# 01_Raspberry_Hat_6_Schematic.net
KiCad netlist of a schematic drawn in EAGLE
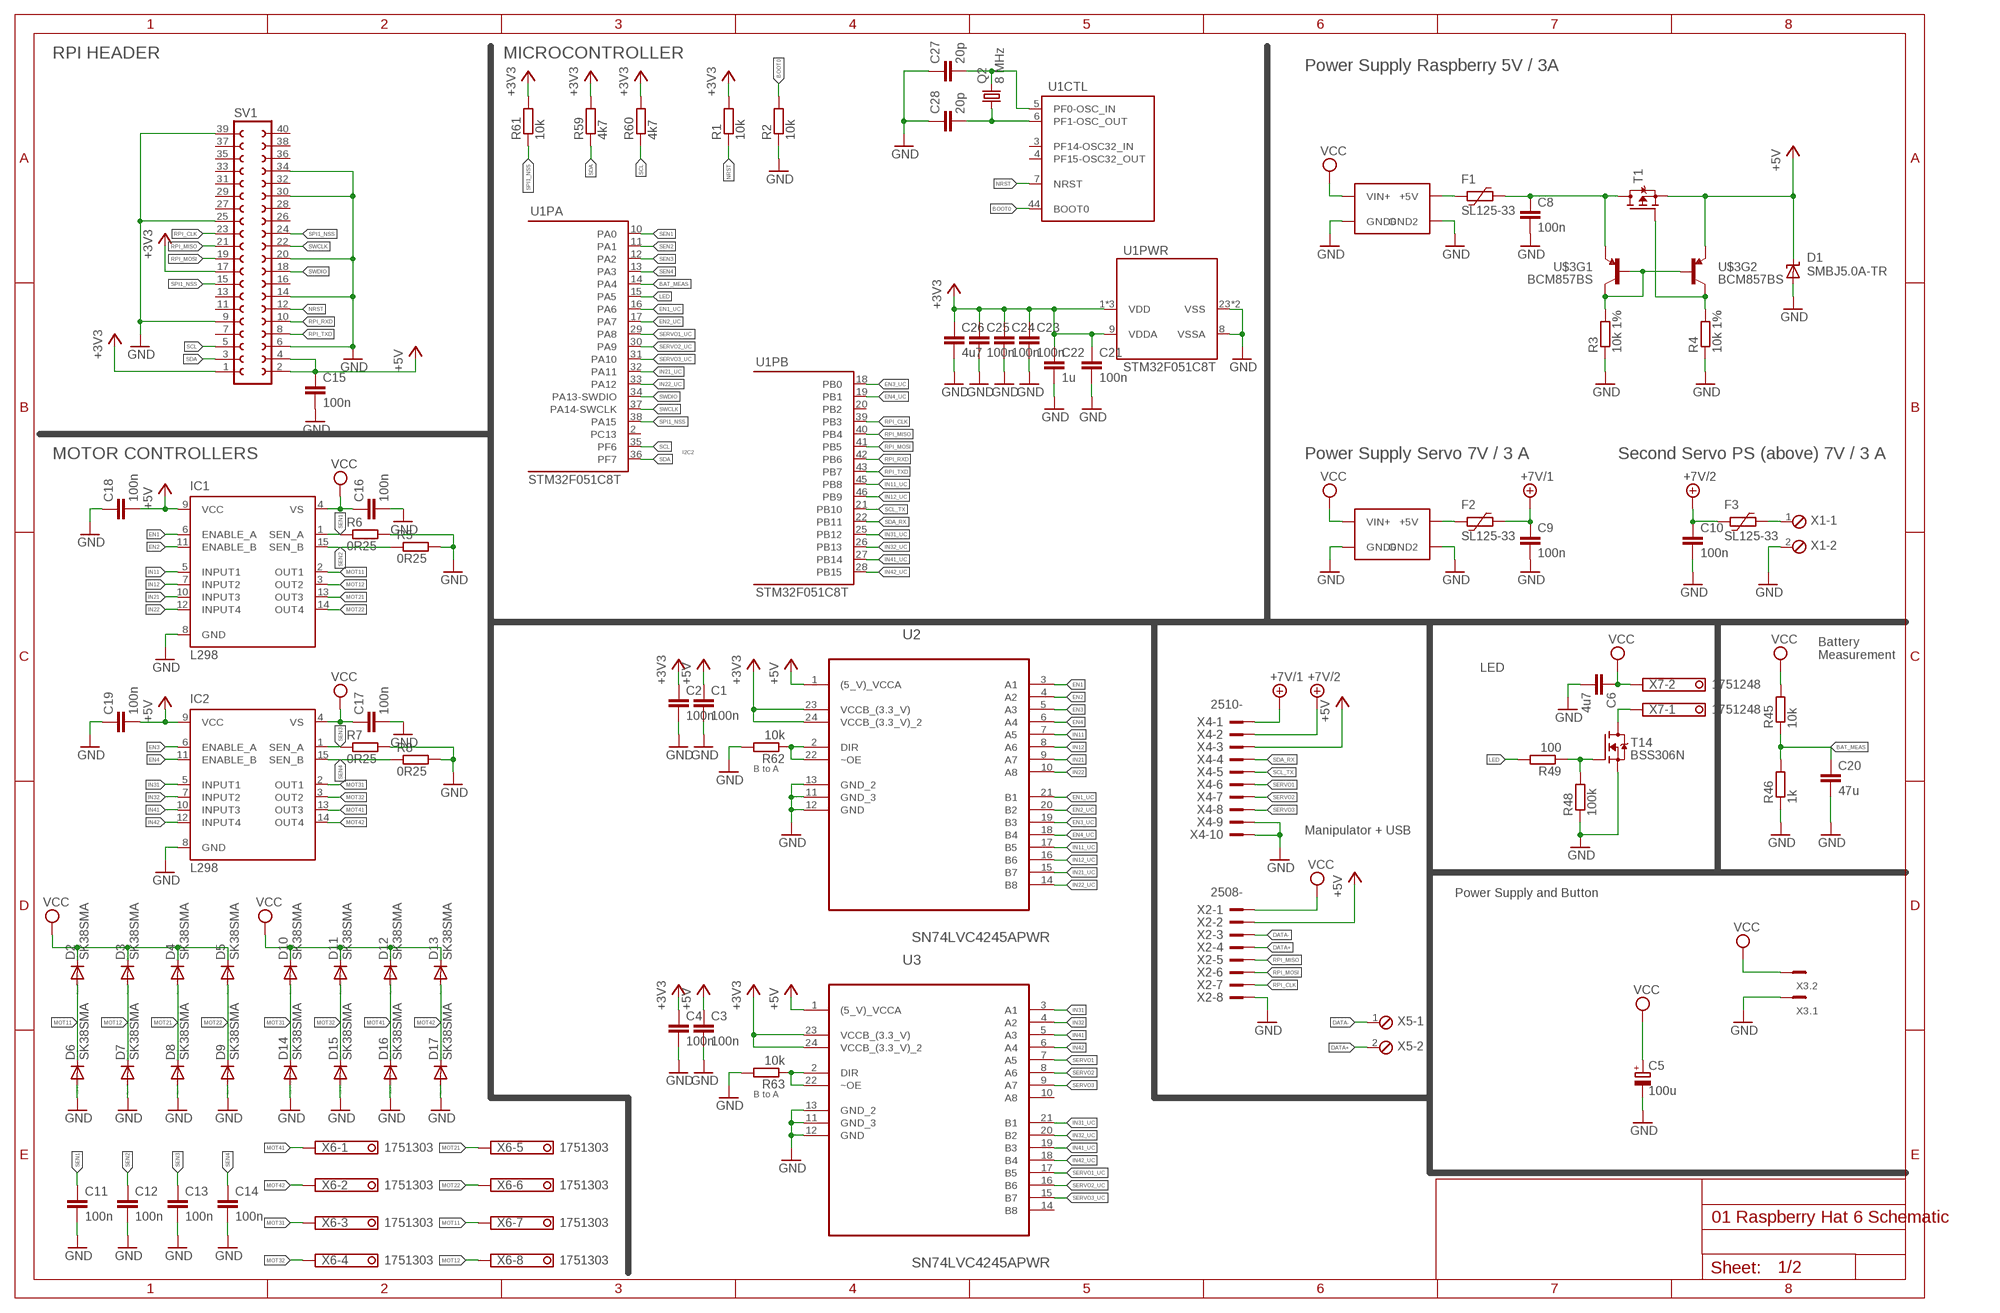
[diagram p0: schematic, sheet 1]
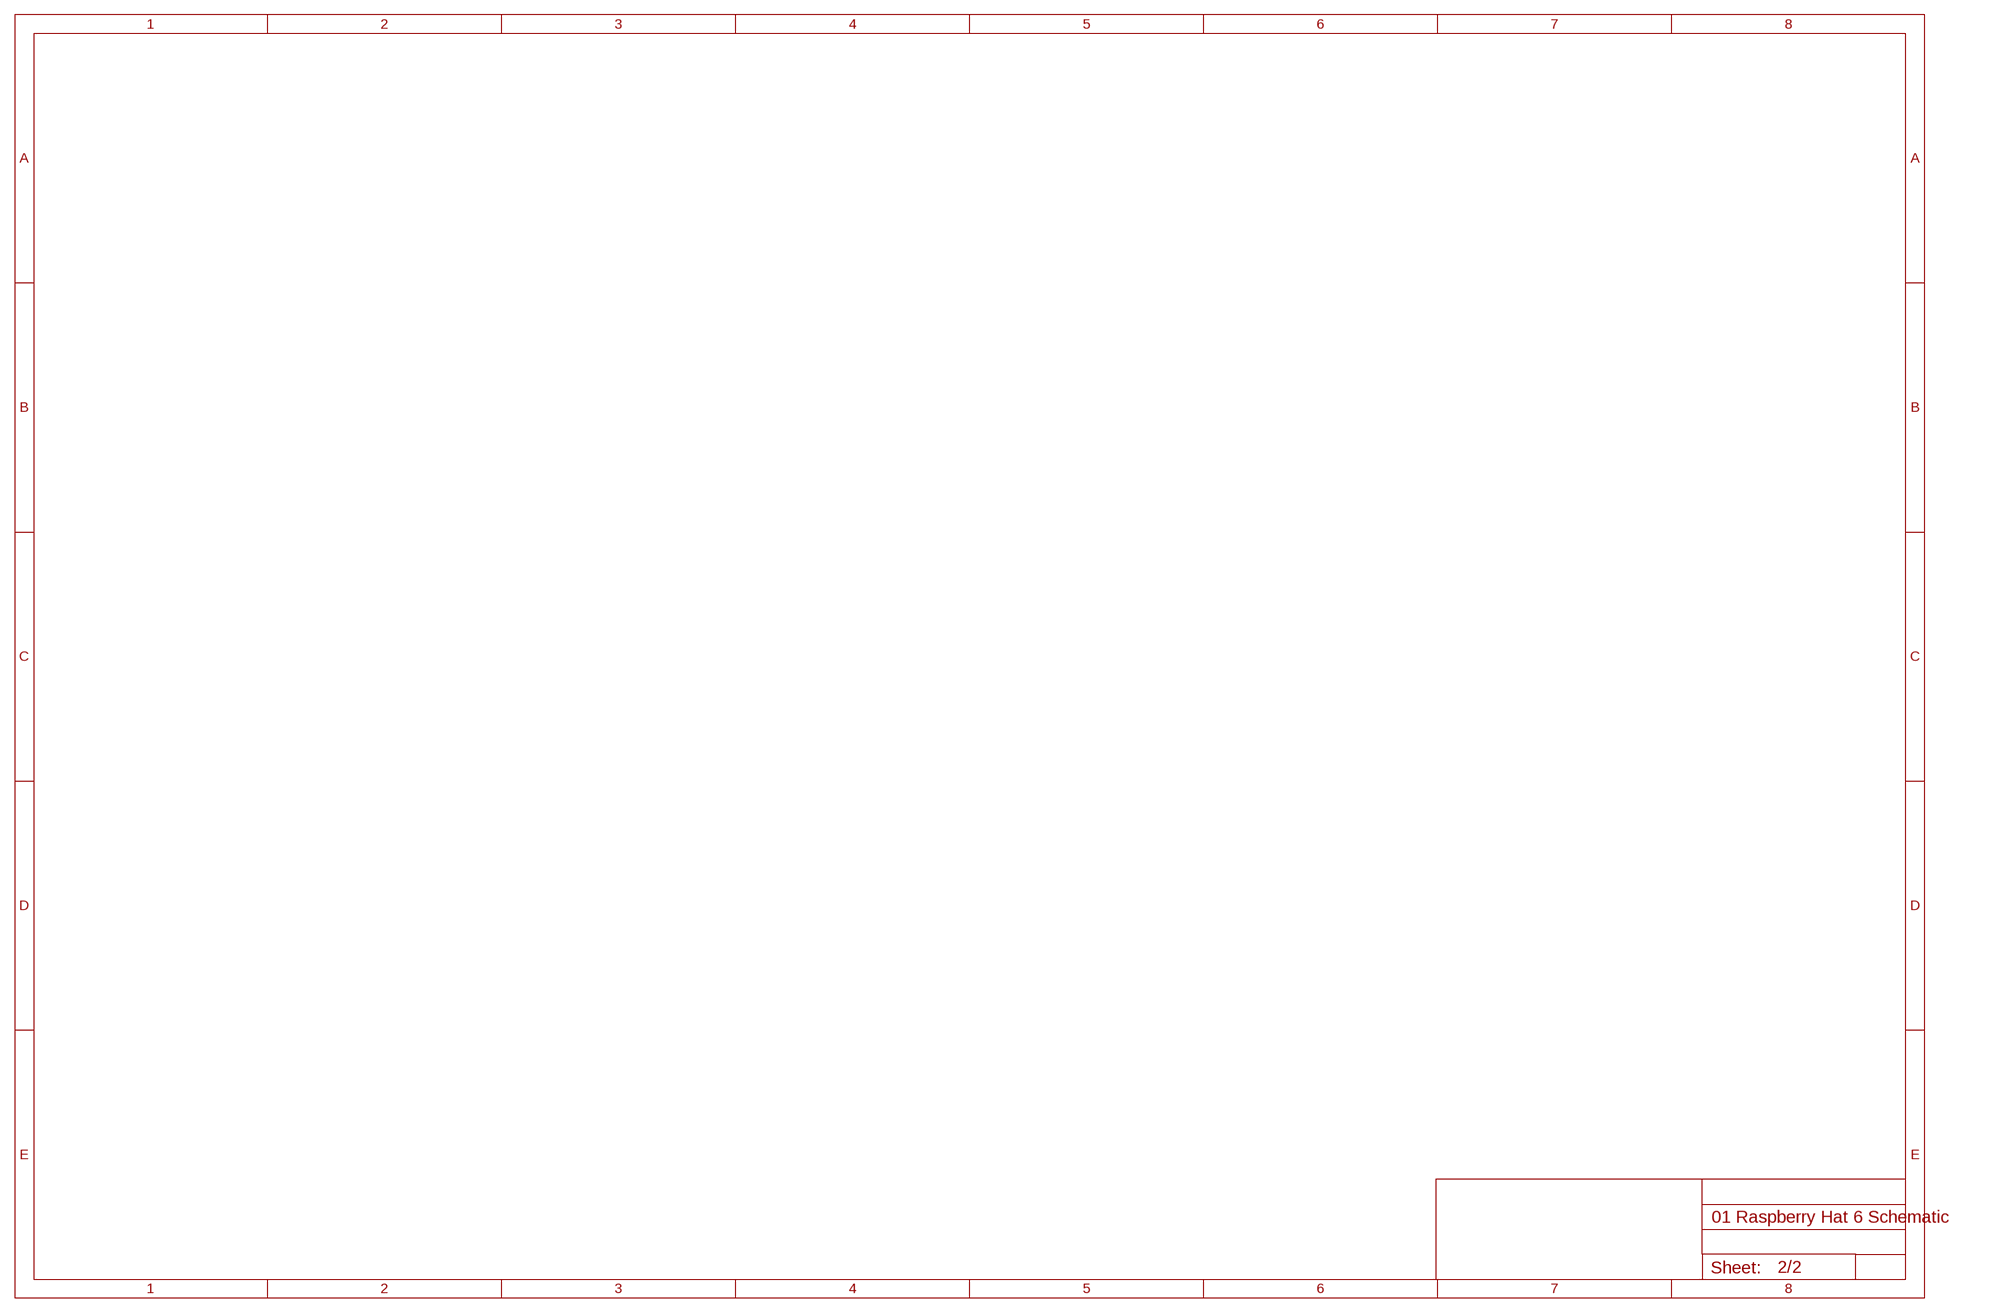
[diagram p1: schematic, sheet 2]

(export (version "E")
  (design (tool "Eeschema 10.0.6"))
  (components
    (comp (ref "C1")
      (value "100n")
      (footprint "eagle-import:C0805")
      (libsource (lib "eagle-import") (part "C-EUC0805"))
    )
    (comp (ref "C2")
      (value "100n")
      (footprint "eagle-import:C0805")
      (libsource (lib "eagle-import") (part "C-EUC0805"))
    )
    (comp (ref "C3")
      (value "100n")
      (footprint "eagle-import:C0805")
      (libsource (lib "eagle-import") (part "C-EUC0805"))
    )
    (comp (ref "C4")
      (value "100n")
      (footprint "eagle-import:C0805")
      (libsource (lib "eagle-import") (part "C-EUC0805"))
    )
    (comp (ref "C5")
      (value "100u")
      (footprint "eagle-import:153CLV-0807")
      (libsource (lib "eagle-import") (part "CPOL-EU153CLV-0807"))
    )
    (comp (ref "C6")
      (value "4u7")
      (footprint "eagle-import:C0805")
      (libsource (lib "eagle-import") (part "C-EUC0805"))
    )
    (comp (ref "C8")
      (value "100n")
      (footprint "eagle-import:C0805")
      (libsource (lib "eagle-import") (part "C-EUC0805"))
    )
    (comp (ref "C9")
      (value "100n")
      (footprint "eagle-import:C0805")
      (libsource (lib "eagle-import") (part "C-EUC0805"))
    )
    (comp (ref "C10")
      (value "100n")
      (footprint "eagle-import:C0805")
      (libsource (lib "eagle-import") (part "C-EUC0805"))
    )
    (comp (ref "C11")
      (value "100n")
      (footprint "eagle-import:C0805")
      (libsource (lib "eagle-import") (part "C-EUC0805"))
    )
    (comp (ref "C12")
      (value "100n")
      (footprint "eagle-import:C0805")
      (libsource (lib "eagle-import") (part "C-EUC0805"))
    )
    (comp (ref "C13")
      (value "100n")
      (footprint "eagle-import:C0805")
      (libsource (lib "eagle-import") (part "C-EUC0805"))
    )
    (comp (ref "C14")
      (value "100n")
      (footprint "eagle-import:C0805")
      (libsource (lib "eagle-import") (part "C-EUC0805"))
    )
    (comp (ref "C15")
      (value "100n")
      (footprint "eagle-import:C0805")
      (libsource (lib "eagle-import") (part "C-EUC0805"))
    )
    (comp (ref "C16")
      (value "100n")
      (footprint "eagle-import:C0805")
      (libsource (lib "eagle-import") (part "C-EUC0805"))
    )
    (comp (ref "C17")
      (value "100n")
      (footprint "eagle-import:C0805")
      (libsource (lib "eagle-import") (part "C-EUC0805"))
    )
    (comp (ref "C18")
      (value "100n")
      (footprint "eagle-import:C0805")
      (libsource (lib "eagle-import") (part "C-EUC0805"))
    )
    (comp (ref "C19")
      (value "100n")
      (footprint "eagle-import:C0805")
      (libsource (lib "eagle-import") (part "C-EUC0805"))
    )
    (comp (ref "C20")
      (value "47u")
      (footprint "eagle-import:C0805")
      (libsource (lib "eagle-import") (part "C-EUC0805"))
    )
    (comp (ref "C21")
      (value "100n")
      (footprint "eagle-import:C0805")
      (libsource (lib "eagle-import") (part "C-EUC0805"))
    )
    (comp (ref "C22")
      (value "1u")
      (footprint "eagle-import:C0805")
      (libsource (lib "eagle-import") (part "C-EUC0805"))
    )
    (comp (ref "C23")
      (value "100n")
      (footprint "eagle-import:C0805")
      (libsource (lib "eagle-import") (part "C-EUC0805"))
    )
    (comp (ref "C24")
      (value "100n")
      (footprint "eagle-import:C0805")
      (libsource (lib "eagle-import") (part "C-EUC0805"))
    )
    (comp (ref "C25")
      (value "100n")
      (footprint "eagle-import:C0805")
      (libsource (lib "eagle-import") (part "C-EUC0805"))
    )
    (comp (ref "C26")
      (value "4u7")
      (footprint "eagle-import:C0805")
      (libsource (lib "eagle-import") (part "C-EUC0805"))
    )
    (comp (ref "C27")
      (value "20p")
      (footprint "eagle-import:C0805")
      (libsource (lib "eagle-import") (part "C-EUC0805"))
    )
    (comp (ref "C28")
      (value "20p")
      (footprint "eagle-import:C0805")
      (libsource (lib "eagle-import") (part "C-EUC0805"))
    )
    (comp (ref "D1")
      (value "SMBJ5.0A-TR")
      (footprint "eagle-import:SMBJ")
      (libsource (lib "eagle-import") (part "SUPPRESSOR-SMBJ"))
    )
    (comp (ref "D2")
      (value "SK38SMA")
      (footprint "eagle-import:DO214AC")
      (libsource (lib "eagle-import") (part "DIODE-DO214AC"))
    )
    (comp (ref "D3")
      (value "SK38SMA")
      (footprint "eagle-import:DO214AC")
      (libsource (lib "eagle-import") (part "DIODE-DO214AC"))
    )
    (comp (ref "D4")
      (value "SK38SMA")
      (footprint "eagle-import:DO214AC")
      (libsource (lib "eagle-import") (part "DIODE-DO214AC"))
    )
    (comp (ref "D5")
      (value "SK38SMA")
      (footprint "eagle-import:DO214AC")
      (libsource (lib "eagle-import") (part "DIODE-DO214AC"))
    )
    (comp (ref "D6")
      (value "SK38SMA")
      (footprint "eagle-import:DO214AC")
      (libsource (lib "eagle-import") (part "DIODE-DO214AC"))
    )
    (comp (ref "D7")
      (value "SK38SMA")
      (footprint "eagle-import:DO214AC")
      (libsource (lib "eagle-import") (part "DIODE-DO214AC"))
    )
    (comp (ref "D8")
      (value "SK38SMA")
      (footprint "eagle-import:DO214AC")
      (libsource (lib "eagle-import") (part "DIODE-DO214AC"))
    )
    (comp (ref "D9")
      (value "SK38SMA")
      (footprint "eagle-import:DO214AC")
      (libsource (lib "eagle-import") (part "DIODE-DO214AC"))
    )
    (comp (ref "D10")
      (value "SK38SMA")
      (footprint "eagle-import:DO214AC")
      (libsource (lib "eagle-import") (part "DIODE-DO214AC"))
    )
    (comp (ref "D11")
      (value "SK38SMA")
      (footprint "eagle-import:DO214AC")
      (libsource (lib "eagle-import") (part "DIODE-DO214AC"))
    )
    (comp (ref "D12")
      (value "SK38SMA")
      (footprint "eagle-import:DO214AC")
      (libsource (lib "eagle-import") (part "DIODE-DO214AC"))
    )
    (comp (ref "D13")
      (value "SK38SMA")
      (footprint "eagle-import:DO214AC")
      (libsource (lib "eagle-import") (part "DIODE-DO214AC"))
    )
    (comp (ref "D14")
      (value "SK38SMA")
      (footprint "eagle-import:DO214AC")
      (libsource (lib "eagle-import") (part "DIODE-DO214AC"))
    )
    (comp (ref "D15")
      (value "SK38SMA")
      (footprint "eagle-import:DO214AC")
      (libsource (lib "eagle-import") (part "DIODE-DO214AC"))
    )
    (comp (ref "D16")
      (value "SK38SMA")
      (footprint "eagle-import:DO214AC")
      (libsource (lib "eagle-import") (part "DIODE-DO214AC"))
    )
    (comp (ref "D17")
      (value "SK38SMA")
      (footprint "eagle-import:DO214AC")
      (libsource (lib "eagle-import") (part "DIODE-DO214AC"))
    )
    (comp (ref "F1")
      (value "SL125-33")
      (footprint "eagle-import:2920L")
      (fields (field (name "MF") "Littelfuse") (field (name "MPN") "2920L050"))
      (libsource (lib "eagle-import") (part "?2920L050"))
    )
    (comp (ref "F2")
      (value "SL125-33")
      (footprint "eagle-import:2920L")
      (fields (field (name "MF") "Littelfuse") (field (name "MPN") "2920L050"))
      (libsource (lib "eagle-import") (part "?2920L050"))
    )
    (comp (ref "F3")
      (value "SL125-33")
      (footprint "eagle-import:2920L")
      (fields (field (name "MF") "Littelfuse") (field (name "MPN") "2920L050"))
      (libsource (lib "eagle-import") (part "?2920L050"))
    )
    (comp (ref "IC1")
      (value "L298")
      (footprint "eagle-import:MULTIWATT-15")
      (fields (field (name "MPN") "L298N"))
      (libsource (lib "eagle-import") (part "L298"))
    )
    (comp (ref "IC2")
      (value "L298")
      (footprint "eagle-import:MULTIWATT-15")
      (fields (field (name "MPN") "L298N"))
      (libsource (lib "eagle-import") (part "L298"))
    )
    (comp (ref "Q2")
      (value "8 MHz")
      (footprint "eagle-import:HC49UP")
      (libsource (lib "eagle-import") (part "CRYSTALHC49UP"))
    )
    (comp (ref "R1")
      (value "10k")
      (footprint "eagle-import:M0805")
      (libsource (lib "eagle-import") (part "resistor_R-EU_M0805"))
    )
    (comp (ref "R2")
      (value "10k")
      (footprint "eagle-import:M0805")
      (libsource (lib "eagle-import") (part "resistor_R-EU_M0805"))
    )
    (comp (ref "R3")
      (value "10k 1%")
      (footprint "eagle-import:M0805")
      (libsource (lib "eagle-import") (part "resistor_R-EU_M0805"))
    )
    (comp (ref "R4")
      (value "10k 1%")
      (footprint "eagle-import:M0805")
      (libsource (lib "eagle-import") (part "resistor_R-EU_M0805"))
    )
    (comp (ref "R5")
      (value "0R25")
      (footprint "eagle-import:R2512")
      (libsource (lib "eagle-import") (part "R-EU_R2512"))
    )
    (comp (ref "R6")
      (value "0R25")
      (footprint "eagle-import:R2512")
      (libsource (lib "eagle-import") (part "R-EU_R2512"))
    )
    (comp (ref "R7")
      (value "0R25")
      (footprint "eagle-import:R2512")
      (libsource (lib "eagle-import") (part "R-EU_R2512"))
    )
    (comp (ref "R8")
      (value "0R25")
      (footprint "eagle-import:R2512")
      (libsource (lib "eagle-import") (part "R-EU_R2512"))
    )
    (comp (ref "R45")
      (value "10k")
      (footprint "eagle-import:M0805")
      (libsource (lib "eagle-import") (part "resistor_R-EU_M0805"))
    )
    (comp (ref "R46")
      (value "1k")
      (footprint "eagle-import:M0805")
      (libsource (lib "eagle-import") (part "resistor_R-EU_M0805"))
    )
    (comp (ref "R48")
      (value "100k")
      (footprint "eagle-import:M0805")
      (libsource (lib "eagle-import") (part "resistor_R-EU_M0805"))
    )
    (comp (ref "R49")
      (value "100")
      (footprint "eagle-import:M0805")
      (libsource (lib "eagle-import") (part "resistor_R-EU_M0805"))
    )
    (comp (ref "R59")
      (value "4k7")
      (footprint "eagle-import:M0805")
      (libsource (lib "eagle-import") (part "resistor_R-EU_M0805"))
    )
    (comp (ref "R60")
      (value "4k7")
      (footprint "eagle-import:M0805")
      (libsource (lib "eagle-import") (part "resistor_R-EU_M0805"))
    )
    (comp (ref "R61")
      (value "10k")
      (footprint "eagle-import:M0805")
      (libsource (lib "eagle-import") (part "resistor_R-EU_M0805"))
    )
    (comp (ref "R62")
      (value "10k")
      (footprint "eagle-import:M0805")
      (libsource (lib "eagle-import") (part "resistor_R-EU_M0805"))
    )
    (comp (ref "R63")
      (value "10k")
      (footprint "eagle-import:M0805")
      (libsource (lib "eagle-import") (part "resistor_R-EU_M0805"))
    )
    (comp (ref "SV1")
      (value "FE20-2")
      (footprint "eagle-import:FE20-2")
      (libsource (lib "eagle-import") (part "FE20-2"))
    )
    (comp (ref "T1")
      (value "MOSFET-P-SOT23")
      (footprint "eagle-import:SOT23")
      (libsource (lib "eagle-import") (part "MOSFET-P-SOT23"))
    )
    (comp (ref "T14")
      (value "BSS306N")
      (footprint "eagle-import:SOT23")
      (libsource (lib "eagle-import") (part "MOSFET-N-SOT23"))
    )
    (comp (ref "U$2")
      (value "LM2596_CONVERTER")
      (footprint "eagle-import:LM2596_CONVERTER")
      (libsource (lib "eagle-import") (part "LM2596_CONVERTER"))
    )
    (comp (ref "U$3")
      (value "BCM857BS")
      (footprint "eagle-import:SOT363")
      (fields (field (name "LINK") "http://www.tme.eu/pl/details/bcm857bs/tranzystory-pnp-smd/nxp/"))
      (libsource (lib "eagle-import") (part "BCM857BS"))
    )
    (comp (ref "U$4")
      (value "LM2596_CONVERTER")
      (footprint "eagle-import:LM2596_CONVERTER")
      (libsource (lib "eagle-import") (part "LM2596_CONVERTER"))
    )
    (comp (ref "U1")
      (value "STM32F051C8T")
      (footprint "eagle-import:LQFP48")
      (libsource (lib "eagle-import") (part "STM32F051CT8"))
    )
    (comp (ref "U2")
      (value "SN74LVC4245APWR")
      (footprint "eagle-import:SOP65P640X120-24N")
      (libsource (lib "eagle-import") (part "SN74LVC4245APWR"))
    )
    (comp (ref "U3")
      (value "SN74LVC4245APWR")
      (footprint "eagle-import:SOP65P640X120-24N")
      (libsource (lib "eagle-import") (part "SN74LVC4245APWR"))
    )
    (comp (ref "X1")
      (value "MPT2")
      (footprint "eagle-import:2POL254")
      (libsource (lib "eagle-import") (part "MPT2"))
    )
    (comp (ref "X2")
      (value "2508-")
      (footprint "eagle-import:PAK100_2500-10")
      (fields (field (name "MF") "3M") (field (name "MPN") "2510-6002UB"))
      (libsource (lib "eagle-import") (part "2508-"))
    )
    (comp (ref "X3")
      (value "MC2")
      (footprint "eagle-import:MC2")
      (libsource (lib "eagle-import") (part "MC2"))
    )
    (comp (ref "X4")
      (value "2510-")
      (footprint "eagle-import:PAK100_2500-10")
      (fields (field (name "MF") "3M") (field (name "MPN") "2510-6002UB"))
      (libsource (lib "eagle-import") (part "2510-"))
    )
    (comp (ref "X5")
      (value "MPT2")
      (footprint "eagle-import:2POL254")
      (libsource (lib "eagle-import") (part "MPT2"))
    )
    (comp (ref "X6")
      (value "1751303")
      (footprint "eagle-import:1751303")
      (libsource (lib "eagle-import") (part "1751303"))
    )
    (comp (ref "X7")
      (value "1751248")
      (footprint "eagle-import:1751248")
      (libsource (lib "eagle-import") (part "1751248"))
    )
  )
  (nets
    (net (code "1") (name "+3V3") (class "Default")
      (node (ref "C2") (pin "1") (pinfunction "1_1") (pintype "passive"))
      (node (ref "C21") (pin "1") (pinfunction "1_1") (pintype "passive"))
      (node (ref "C22") (pin "1") (pinfunction "1_1") (pintype "passive"))
      (node (ref "C23") (pin "1") (pinfunction "1_1") (pintype "passive"))
      (node (ref "C24") (pin "1") (pinfunction "1_1") (pintype "passive"))
      (node (ref "C25") (pin "1") (pinfunction "1_1") (pintype "passive"))
      (node (ref "C26") (pin "1") (pinfunction "1_1") (pintype "passive"))
      (node (ref "C4") (pin "1") (pinfunction "1_1") (pintype "passive"))
      (node (ref "R1") (pin "2") (pinfunction "2_2") (pintype "passive"))
      (node (ref "R59") (pin "2") (pinfunction "2_2") (pintype "passive"))
      (node (ref "R60") (pin "2") (pinfunction "2_2") (pintype "passive"))
      (node (ref "R61") (pin "2") (pinfunction "2_2") (pintype "passive"))
      (node (ref "SV1") (pin "1") (pinfunction "1_1") (pintype "passive"))
      (node (ref "SV1") (pin "17") (pinfunction "17_17") (pintype "passive"))
      (node (ref "U1") (pin "1") (pinfunction "VDD_1") (pintype "power_in"))
      (node (ref "U1") (pin "24") (pinfunction "VDD_24") (pintype "power_in"))
      (node (ref "U1") (pin "48") (pinfunction "VDD_48") (pintype "power_in"))
      (node (ref "U1") (pin "9") (pinfunction "VDDA_9") (pintype "power_in"))
      (node (ref "U2") (pin "23") (pinfunction "VCCB_(3.3_V)_23") (pintype "power_in"))
      (node (ref "U2") (pin "24") (pinfunction "VCCB_(3.3_V)_2_24") (pintype "power_in"))
      (node (ref "U3") (pin "23") (pinfunction "VCCB_(3.3_V)_23") (pintype "power_in"))
      (node (ref "U3") (pin "24") (pinfunction "VCCB_(3.3_V)_2_24") (pintype "power_in"))
    )
    (net (code "2") (name "+5V") (class "Default")
      (node (ref "C1") (pin "1") (pinfunction "1_1") (pintype "passive"))
      (node (ref "C15") (pin "1") (pinfunction "1_1") (pintype "passive"))
      (node (ref "C18") (pin "2") (pinfunction "2_2") (pintype "passive"))
      (node (ref "C19") (pin "2") (pinfunction "2_2") (pintype "passive"))
      (node (ref "C3") (pin "1") (pinfunction "1_1") (pintype "passive"))
      (node (ref "D1") (pin "C") (pinfunction "C_C") (pintype "passive"))
      (node (ref "IC1") (pin "9") (pinfunction "VCC_9") (pintype "power_in"))
      (node (ref "IC2") (pin "9") (pinfunction "VCC_9") (pintype "power_in"))
      (node (ref "SV1") (pin "2") (pinfunction "2_2") (pintype "passive"))
      (node (ref "SV1") (pin "4") (pinfunction "4_4") (pintype "passive"))
      (node (ref "T1") (pin "2") (pinfunction "S_2") (pintype "passive"))
      (node (ref "U$3") (pin "4") (pinfunction "E_4") (pintype "passive"))
      (node (ref "U2") (pin "1") (pinfunction "(5_V)_VCCA_1") (pintype "power_in"))
      (node (ref "U3") (pin "1") (pinfunction "(5_V)_VCCA_1") (pintype "power_in"))
      (node (ref "X2") (pin "2") (pinfunction "KL_2") (pintype "passive"))
      (node (ref "X4") (pin "3") (pinfunction "KL_3") (pintype "passive"))
    )
    (net (code "3") (name "+7V{slash}1") (class "Default")
      (node (ref "C9") (pin "1") (pinfunction "1_1") (pintype "passive"))
      (node (ref "F2") (pin "1") (pinfunction "1_1") (pintype "passive"))
      (node (ref "X4") (pin "1") (pinfunction "KL_1") (pintype "passive"))
    )
    (net (code "4") (name "+7V{slash}2") (class "Default")
      (node (ref "C10") (pin "1") (pinfunction "1_1") (pintype "passive"))
      (node (ref "F3") (pin "2") (pinfunction "2_2") (pintype "passive"))
      (node (ref "X4") (pin "2") (pinfunction "KL_2") (pintype "passive"))
    )
    (net (code "5") (name "BAT_MEAS") (class "Default")
      (node (ref "C20") (pin "1") (pinfunction "1_1") (pintype "passive"))
      (node (ref "R45") (pin "1") (pinfunction "1_1") (pintype "passive"))
      (node (ref "R46") (pin "2") (pinfunction "2_2") (pintype "passive"))
      (node (ref "U1") (pin "14") (pinfunction "PA4_14") (pintype "bidirectional"))
    )
    (net (code "6") (name "BOOT0") (class "Default")
      (node (ref "R2") (pin "2") (pinfunction "2_2") (pintype "passive"))
      (node (ref "U1") (pin "44") (pinfunction "BOOT0_44") (pintype "bidirectional"))
    )
    (net (code "7") (name "DATA+") (class "Default")
      (node (ref "X2") (pin "4") (pinfunction "KL_4") (pintype "passive"))
      (node (ref "X5") (pin "2") (pinfunction "1_2") (pintype "passive"))
    )
    (net (code "8") (name "DATA-") (class "Default")
      (node (ref "X2") (pin "3") (pinfunction "KL_3") (pintype "passive"))
      (node (ref "X5") (pin "1") (pinfunction "1_1") (pintype "passive"))
    )
    (net (code "9") (name "EN1") (class "Default")
      (node (ref "IC1") (pin "6") (pinfunction "ENABLE_A_6") (pintype "input"))
      (node (ref "U2") (pin "3") (pinfunction "A1_3") (pintype "output"))
    )
    (net (code "10") (name "EN1_UC") (class "Default")
      (node (ref "U1") (pin "16") (pinfunction "PA6_16") (pintype "bidirectional"))
      (node (ref "U2") (pin "21") (pinfunction "B1_21") (pintype "output"))
    )
    (net (code "11") (name "EN2") (class "Default")
      (node (ref "IC1") (pin "11") (pinfunction "ENABLE_B_11") (pintype "input"))
      (node (ref "U2") (pin "4") (pinfunction "A2_4") (pintype "output"))
    )
    (net (code "12") (name "EN2_UC") (class "Default")
      (node (ref "U1") (pin "17") (pinfunction "PA7_17") (pintype "bidirectional"))
      (node (ref "U2") (pin "20") (pinfunction "B2_20") (pintype "output"))
    )
    (net (code "13") (name "EN3") (class "Default")
      (node (ref "IC2") (pin "6") (pinfunction "ENABLE_A_6") (pintype "input"))
      (node (ref "U2") (pin "5") (pinfunction "A3_5") (pintype "output"))
    )
    (net (code "14") (name "EN3_UC") (class "Default")
      (node (ref "U1") (pin "18") (pinfunction "PB0_18") (pintype "bidirectional"))
      (node (ref "U2") (pin "19") (pinfunction "B3_19") (pintype "output"))
    )
    (net (code "15") (name "EN4") (class "Default")
      (node (ref "IC2") (pin "11") (pinfunction "ENABLE_B_11") (pintype "input"))
      (node (ref "U2") (pin "6") (pinfunction "A4_6") (pintype "output"))
    )
    (net (code "16") (name "EN4_UC") (class "Default")
      (node (ref "U1") (pin "19") (pinfunction "PB1_19") (pintype "bidirectional"))
      (node (ref "U2") (pin "18") (pinfunction "B4_18") (pintype "output"))
    )
    (net (code "17") (name "GND") (class "Default")
      (node (ref "C1") (pin "2") (pinfunction "2_2") (pintype "passive"))
      (node (ref "C10") (pin "2") (pinfunction "2_2") (pintype "passive"))
      (node (ref "C11") (pin "2") (pinfunction "2_2") (pintype "passive"))
      (node (ref "C12") (pin "2") (pinfunction "2_2") (pintype "passive"))
      (node (ref "C13") (pin "2") (pinfunction "2_2") (pintype "passive"))
      (node (ref "C14") (pin "2") (pinfunction "2_2") (pintype "passive"))
      (node (ref "C15") (pin "2") (pinfunction "2_2") (pintype "passive"))
      (node (ref "C16") (pin "2") (pinfunction "2_2") (pintype "passive"))
      (node (ref "C17") (pin "2") (pinfunction "2_2") (pintype "passive"))
      (node (ref "C18") (pin "1") (pinfunction "1_1") (pintype "passive"))
      (node (ref "C19") (pin "1") (pinfunction "1_1") (pintype "passive"))
      (node (ref "C2") (pin "2") (pinfunction "2_2") (pintype "passive"))
      (node (ref "C20") (pin "2") (pinfunction "2_2") (pintype "passive"))
      (node (ref "C21") (pin "2") (pinfunction "2_2") (pintype "passive"))
      (node (ref "C22") (pin "2") (pinfunction "2_2") (pintype "passive"))
      (node (ref "C23") (pin "2") (pinfunction "2_2") (pintype "passive"))
      (node (ref "C24") (pin "2") (pinfunction "2_2") (pintype "passive"))
      (node (ref "C25") (pin "2") (pinfunction "2_2") (pintype "passive"))
      (node (ref "C26") (pin "2") (pinfunction "2_2") (pintype "passive"))
      (node (ref "C27") (pin "1") (pinfunction "1_1") (pintype "passive"))
      (node (ref "C28") (pin "1") (pinfunction "1_1") (pintype "passive"))
      (node (ref "C3") (pin "2") (pinfunction "2_2") (pintype "passive"))
      (node (ref "C4") (pin "2") (pinfunction "2_2") (pintype "passive"))
      (node (ref "C5") (pin "-") (pinfunction "-_-") (pintype "passive"))
      (node (ref "C6") (pin "2") (pinfunction "2_2") (pintype "passive"))
      (node (ref "C8") (pin "2") (pinfunction "2_2") (pintype "passive"))
      (node (ref "C9") (pin "2") (pinfunction "2_2") (pintype "passive"))
      (node (ref "D1") (pin "A") (pinfunction "A_A") (pintype "passive"))
      (node (ref "D14") (pin "A") (pinfunction "A_A") (pintype "passive"))
      (node (ref "D15") (pin "A") (pinfunction "A_A") (pintype "passive"))
      (node (ref "D16") (pin "A") (pinfunction "A_A") (pintype "passive"))
      (node (ref "D17") (pin "A") (pinfunction "A_A") (pintype "passive"))
      (node (ref "D6") (pin "A") (pinfunction "A_A") (pintype "passive"))
      (node (ref "D7") (pin "A") (pinfunction "A_A") (pintype "passive"))
      (node (ref "D8") (pin "A") (pinfunction "A_A") (pintype "passive"))
      (node (ref "D9") (pin "A") (pinfunction "A_A") (pintype "passive"))
      (node (ref "IC1") (pin "8") (pinfunction "GND_8") (pintype "power_in"))
      (node (ref "IC2") (pin "8") (pinfunction "GND_8") (pintype "power_in"))
      (node (ref "R2") (pin "1") (pinfunction "1_1") (pintype "passive"))
      (node (ref "R3") (pin "1") (pinfunction "1_1") (pintype "passive"))
      (node (ref "R4") (pin "1") (pinfunction "1_1") (pintype "passive"))
      (node (ref "R46") (pin "1") (pinfunction "1_1") (pintype "passive"))
      (node (ref "R48") (pin "1") (pinfunction "1_1") (pintype "passive"))
      (node (ref "R5") (pin "2") (pinfunction "2_2") (pintype "passive"))
      (node (ref "R6") (pin "2") (pinfunction "2_2") (pintype "passive"))
      (node (ref "R62") (pin "2") (pinfunction "2_2") (pintype "passive"))
      (node (ref "R63") (pin "2") (pinfunction "2_2") (pintype "passive"))
      (node (ref "R7") (pin "2") (pinfunction "2_2") (pintype "passive"))
      (node (ref "R8") (pin "2") (pinfunction "2_2") (pintype "passive"))
      (node (ref "SV1") (pin "14") (pinfunction "14_14") (pintype "passive"))
      (node (ref "SV1") (pin "20") (pinfunction "20_20") (pintype "passive"))
      (node (ref "SV1") (pin "25") (pinfunction "25_25") (pintype "passive"))
      (node (ref "SV1") (pin "30") (pinfunction "30_30") (pintype "passive"))
      (node (ref "SV1") (pin "34") (pinfunction "34_34") (pintype "passive"))
      (node (ref "SV1") (pin "39") (pinfunction "39_39") (pintype "passive"))
      (node (ref "SV1") (pin "6") (pinfunction "6_6") (pintype "passive"))
      (node (ref "SV1") (pin "9") (pinfunction "9_9") (pintype "passive"))
      (node (ref "T14") (pin "2") (pinfunction "S_2") (pintype "passive"))
      (node (ref "U$2") (pin "GND") (pinfunction "GND0_GND") (pintype "input"))
      (node (ref "U$2") (pin "GND1") (pinfunction "GND2_GND1") (pintype "output"))
      (node (ref "U$4") (pin "GND") (pinfunction "GND0_GND") (pintype "input"))
      (node (ref "U$4") (pin "GND1") (pinfunction "GND2_GND1") (pintype "output"))
      (node (ref "U1") (pin "23") (pinfunction "VSS_23") (pintype "power_in"))
      (node (ref "U1") (pin "47") (pinfunction "VSS_47") (pintype "power_in"))
      (node (ref "U1") (pin "8") (pinfunction "VSSA_8") (pintype "power_in"))
      (node (ref "U2") (pin "11") (pinfunction "GND_3_11") (pintype "passive"))
      (node (ref "U2") (pin "12") (pinfunction "GND_12") (pintype "passive"))
      (node (ref "U2") (pin "13") (pinfunction "GND_2_13") (pintype "passive"))
      (node (ref "U3") (pin "11") (pinfunction "GND_3_11") (pintype "passive"))
      (node (ref "U3") (pin "12") (pinfunction "GND_12") (pintype "passive"))
      (node (ref "U3") (pin "13") (pinfunction "GND_2_13") (pintype "passive"))
      (node (ref "X1") (pin "2") (pinfunction "1_2") (pintype "passive"))
      (node (ref "X2") (pin "8") (pinfunction "KL_8") (pintype "passive"))
      (node (ref "X3") (pin "1") (pinfunction "SK_1") (pintype "passive"))
      (node (ref "X4") (pin "10") (pinfunction "KL_10") (pintype "passive"))
      (node (ref "X4") (pin "9") (pinfunction "KL_9") (pintype "passive"))
    )
    (net (code "18") (name "IN11") (class "Default")
      (node (ref "IC1") (pin "5") (pinfunction "INPUT1_5") (pintype "input"))
      (node (ref "U2") (pin "7") (pinfunction "A5_7") (pintype "output"))
    )
    (net (code "19") (name "IN11_UC") (class "Default")
      (node (ref "U1") (pin "45") (pinfunction "PB8_45") (pintype "bidirectional"))
      (node (ref "U2") (pin "17") (pinfunction "B5_17") (pintype "output"))
    )
    (net (code "20") (name "IN12") (class "Default")
      (node (ref "IC1") (pin "7") (pinfunction "INPUT2_7") (pintype "input"))
      (node (ref "U2") (pin "8") (pinfunction "A6_8") (pintype "output"))
    )
    (net (code "21") (name "IN12_UC") (class "Default")
      (node (ref "U1") (pin "46") (pinfunction "PB9_46") (pintype "bidirectional"))
      (node (ref "U2") (pin "16") (pinfunction "B6_16") (pintype "output"))
    )
    (net (code "22") (name "IN21") (class "Default")
      (node (ref "IC1") (pin "10") (pinfunction "INPUT3_10") (pintype "input"))
      (node (ref "U2") (pin "9") (pinfunction "A7_9") (pintype "output"))
    )
    (net (code "23") (name "IN21_UC") (class "Default")
      (node (ref "U1") (pin "32") (pinfunction "PA11_32") (pintype "bidirectional"))
      (node (ref "U2") (pin "15") (pinfunction "B7_15") (pintype "output"))
    )
    (net (code "24") (name "IN22") (class "Default")
      (node (ref "IC1") (pin "12") (pinfunction "INPUT4_12") (pintype "input"))
      (node (ref "U2") (pin "10") (pinfunction "A8_10") (pintype "output"))
    )
    (net (code "25") (name "IN22_UC") (class "Default")
      (node (ref "U1") (pin "33") (pinfunction "PA12_33") (pintype "bidirectional"))
      (node (ref "U2") (pin "14") (pinfunction "B8_14") (pintype "output"))
    )
    (net (code "26") (name "IN31") (class "Default")
      (node (ref "IC2") (pin "5") (pinfunction "INPUT1_5") (pintype "input"))
      (node (ref "U3") (pin "3") (pinfunction "A1_3") (pintype "output"))
    )
    (net (code "27") (name "IN31_UC") (class "Default")
      (node (ref "U1") (pin "25") (pinfunction "PB12_25") (pintype "bidirectional"))
      (node (ref "U3") (pin "21") (pinfunction "B1_21") (pintype "output"))
    )
    (net (code "28") (name "IN32") (class "Default")
      (node (ref "IC2") (pin "7") (pinfunction "INPUT2_7") (pintype "input"))
      (node (ref "U3") (pin "4") (pinfunction "A2_4") (pintype "output"))
    )
    (net (code "29") (name "IN32_UC") (class "Default")
      (node (ref "U1") (pin "26") (pinfunction "PB13_26") (pintype "bidirectional"))
      (node (ref "U3") (pin "20") (pinfunction "B2_20") (pintype "output"))
    )
    (net (code "30") (name "IN41") (class "Default")
      (node (ref "IC2") (pin "10") (pinfunction "INPUT3_10") (pintype "input"))
      (node (ref "U3") (pin "5") (pinfunction "A3_5") (pintype "output"))
    )
    (net (code "31") (name "IN41_UC") (class "Default")
      (node (ref "U1") (pin "27") (pinfunction "PB14_27") (pintype "bidirectional"))
      (node (ref "U3") (pin "19") (pinfunction "B3_19") (pintype "output"))
    )
    (net (code "32") (name "IN42") (class "Default")
      (node (ref "IC2") (pin "12") (pinfunction "INPUT4_12") (pintype "input"))
      (node (ref "U3") (pin "6") (pinfunction "A4_6") (pintype "output"))
    )
    (net (code "33") (name "IN42_UC") (class "Default")
      (node (ref "U1") (pin "28") (pinfunction "PB15_28") (pintype "bidirectional"))
      (node (ref "U3") (pin "18") (pinfunction "B4_18") (pintype "output"))
    )
    (net (code "34") (name "LED") (class "Default")
      (node (ref "R49") (pin "2") (pinfunction "2_2") (pintype "passive"))
      (node (ref "U1") (pin "15") (pinfunction "PA5_15") (pintype "bidirectional"))
    )
    (net (code "35") (name "MOT11") (class "Default")
      (node (ref "D2") (pin "A") (pinfunction "A_A") (pintype "passive"))
      (node (ref "D6") (pin "C") (pinfunction "C_C") (pintype "passive"))
      (node (ref "IC1") (pin "2") (pinfunction "OUT1_2") (pintype "output"))
      (node (ref "X6") (pin "7") (pinfunction "K_7") (pintype "passive"))
    )
    (net (code "36") (name "MOT12") (class "Default")
      (node (ref "D3") (pin "A") (pinfunction "A_A") (pintype "passive"))
      (node (ref "D7") (pin "C") (pinfunction "C_C") (pintype "passive"))
      (node (ref "IC1") (pin "3") (pinfunction "OUT2_3") (pintype "output"))
      (node (ref "X6") (pin "8") (pinfunction "K_8") (pintype "passive"))
    )
    (net (code "37") (name "MOT21") (class "Default")
      (node (ref "D4") (pin "A") (pinfunction "A_A") (pintype "passive"))
      (node (ref "D8") (pin "C") (pinfunction "C_C") (pintype "passive"))
      (node (ref "IC1") (pin "13") (pinfunction "OUT3_13") (pintype "output"))
      (node (ref "X6") (pin "5") (pinfunction "K_5") (pintype "passive"))
    )
    (net (code "38") (name "MOT22") (class "Default")
      (node (ref "D5") (pin "A") (pinfunction "A_A") (pintype "passive"))
      (node (ref "D9") (pin "C") (pinfunction "C_C") (pintype "passive"))
      (node (ref "IC1") (pin "14") (pinfunction "OUT4_14") (pintype "output"))
      (node (ref "X6") (pin "6") (pinfunction "K_6") (pintype "passive"))
    )
    (net (code "39") (name "MOT31") (class "Default")
      (node (ref "D10") (pin "A") (pinfunction "A_A") (pintype "passive"))
      (node (ref "D14") (pin "C") (pinfunction "C_C") (pintype "passive"))
      (node (ref "IC2") (pin "2") (pinfunction "OUT1_2") (pintype "output"))
      (node (ref "X6") (pin "3") (pinfunction "K_3") (pintype "passive"))
    )
    (net (code "40") (name "MOT32") (class "Default")
      (node (ref "D11") (pin "A") (pinfunction "A_A") (pintype "passive"))
      (node (ref "D15") (pin "C") (pinfunction "C_C") (pintype "passive"))
      (node (ref "IC2") (pin "3") (pinfunction "OUT2_3") (pintype "output"))
      (node (ref "X6") (pin "4") (pinfunction "K_4") (pintype "passive"))
    )
    (net (code "41") (name "MOT41") (class "Default")
      (node (ref "D12") (pin "A") (pinfunction "A_A") (pintype "passive"))
      (node (ref "D16") (pin "C") (pinfunction "C_C") (pintype "passive"))
      (node (ref "IC2") (pin "13") (pinfunction "OUT3_13") (pintype "output"))
      (node (ref "X6") (pin "1") (pinfunction "K_1") (pintype "passive"))
    )
    (net (code "42") (name "MOT42") (class "Default")
      (node (ref "D13") (pin "A") (pinfunction "A_A") (pintype "passive"))
      (node (ref "D17") (pin "C") (pinfunction "C_C") (pintype "passive"))
      (node (ref "IC2") (pin "14") (pinfunction "OUT4_14") (pintype "output"))
      (node (ref "X6") (pin "2") (pinfunction "K_2") (pintype "passive"))
    )
    (net (code "43") (name "NRST") (class "Default")
      (node (ref "R1") (pin "1") (pinfunction "1_1") (pintype "passive"))
      (node (ref "SV1") (pin "12") (pinfunction "12_12") (pintype "passive"))
      (node (ref "U1") (pin "7") (pinfunction "NRST_7") (pintype "bidirectional"))
    )
    (net (code "44") (name "Net-(F1-Pad2)") (class "Default")
      (node (ref "F1") (pin "2") (pinfunction "2_2") (pintype "passive"))
      (node (ref "U$2") (pin "+5V") (pinfunction "+5V_+5V") (pintype "output"))
    )
    (net (code "45") (name "Net-(F2-Pad2)") (class "Default")
      (node (ref "F2") (pin "2") (pinfunction "2_2") (pintype "passive"))
      (node (ref "U$4") (pin "+5V") (pinfunction "+5V_+5V") (pintype "output"))
    )
    (net (code "46") (name "Net-(F3-Pad1)") (class "Default")
      (node (ref "F3") (pin "1") (pinfunction "1_1") (pintype "passive"))
      (node (ref "X1") (pin "1") (pinfunction "1_1") (pintype "passive"))
    )
    (net (code "47") (name "Net-(T1-D)") (class "Default")
      (node (ref "C8") (pin "1") (pinfunction "1_1") (pintype "passive"))
      (node (ref "F1") (pin "1") (pinfunction "1_1") (pintype "passive"))
      (node (ref "T1") (pin "3") (pinfunction "D_3") (pintype "passive"))
      (node (ref "U$3") (pin "1") (pinfunction "E_1") (pintype "passive"))
    )
    (net (code "48") (name "Net-(T1-G)") (class "Default")
      (node (ref "R4") (pin "2") (pinfunction "2_2") (pintype "passive"))
      (node (ref "T1") (pin "1") (pinfunction "G_1") (pintype "passive"))
      (node (ref "U$3") (pin "3") (pinfunction "C_3") (pintype "passive"))
    )
    (net (code "49") (name "Net-(T14-D)") (class "Default")
      (node (ref "T14") (pin "3") (pinfunction "D_3") (pintype "passive"))
      (node (ref "X7") (pin "1") (pinfunction "K_1") (pintype "passive"))
    )
    (net (code "50") (name "Net-(T14-G)") (class "Default")
      (node (ref "R48") (pin "2") (pinfunction "2_2") (pintype "passive"))
      (node (ref "R49") (pin "1") (pinfunction "1_1") (pintype "passive"))
      (node (ref "T14") (pin "1") (pinfunction "G_1") (pintype "passive"))
    )
    (net (code "51") (name "Net-(U$3A-B)") (class "Default")
      (node (ref "R3") (pin "2") (pinfunction "2_2") (pintype "passive"))
      (node (ref "U$3") (pin "2") (pinfunction "B_2") (pintype "passive"))
      (node (ref "U$3") (pin "5") (pinfunction "B_5") (pintype "passive"))
      (node (ref "U$3") (pin "6") (pinfunction "C_6") (pintype "passive"))
    )
    (net (code "52") (name "Net-(U1A-PF0-OSC_IN)") (class "Default")
      (node (ref "C27") (pin "2") (pinfunction "2_2") (pintype "passive"))
      (node (ref "Q2") (pin "2") (pinfunction "2_2") (pintype "passive"))
      (node (ref "U1") (pin "5") (pinfunction "PF0-OSC_IN_5") (pintype "bidirectional"))
    )
    (net (code "53") (name "Net-(U1A-PF1-OSC_OUT)") (class "Default")
      (node (ref "C28") (pin "2") (pinfunction "2_2") (pintype "passive"))
      (node (ref "Q2") (pin "1") (pinfunction "1_1") (pintype "passive"))
      (node (ref "U1") (pin "6") (pinfunction "PF1-OSC_OUT_6") (pintype "bidirectional"))
    )
    (net (code "54") (name "Net-(U2-DIR)") (class "Default")
      (node (ref "R62") (pin "1") (pinfunction "1_1") (pintype "passive"))
      (node (ref "U2") (pin "2") (pinfunction "DIR_2") (pintype "input"))
      (node (ref "U2") (pin "22") (pinfunction "~{OE}_22") (pintype "input"))
    )
    (net (code "55") (name "Net-(U3-DIR)") (class "Default")
      (node (ref "R63") (pin "1") (pinfunction "1_1") (pintype "passive"))
      (node (ref "U3") (pin "2") (pinfunction "DIR_2") (pintype "input"))
      (node (ref "U3") (pin "22") (pinfunction "~{OE}_22") (pintype "input"))
    )
    (net (code "56") (name "RPI_CLK") (class "Default")
      (node (ref "SV1") (pin "23") (pinfunction "23_23") (pintype "passive"))
      (node (ref "U1") (pin "39") (pinfunction "PB3_39") (pintype "bidirectional"))
      (node (ref "X2") (pin "7") (pinfunction "KL_7") (pintype "passive"))
    )
    (net (code "57") (name "RPI_MISO") (class "Default")
      (node (ref "SV1") (pin "21") (pinfunction "21_21") (pintype "passive"))
      (node (ref "U1") (pin "40") (pinfunction "PB4_40") (pintype "bidirectional"))
      (node (ref "X2") (pin "5") (pinfunction "KL_5") (pintype "passive"))
    )
    (net (code "58") (name "RPI_MOSI") (class "Default")
      (node (ref "SV1") (pin "19") (pinfunction "19_19") (pintype "passive"))
      (node (ref "U1") (pin "41") (pinfunction "PB5_41") (pintype "bidirectional"))
      (node (ref "X2") (pin "6") (pinfunction "KL_6") (pintype "passive"))
    )
    (net (code "59") (name "RPI_RXD") (class "Default")
      (node (ref "SV1") (pin "10") (pinfunction "10_10") (pintype "passive"))
      (node (ref "U1") (pin "42") (pinfunction "PB6_42") (pintype "bidirectional"))
    )
    (net (code "60") (name "RPI_TXD") (class "Default")
      (node (ref "SV1") (pin "8") (pinfunction "8_8") (pintype "passive"))
      (node (ref "U1") (pin "43") (pinfunction "PB7_43") (pintype "bidirectional"))
    )
    (net (code "61") (name "SCL") (class "Default")
      (node (ref "R60") (pin "1") (pinfunction "1_1") (pintype "passive"))
      (node (ref "SV1") (pin "5") (pinfunction "5_5") (pintype "passive"))
      (node (ref "U1") (pin "35") (pinfunction "PF6_35") (pintype "bidirectional"))
    )
    (net (code "62") (name "SCL_TX") (class "Default")
      (node (ref "U1") (pin "21") (pinfunction "PB10_21") (pintype "bidirectional"))
      (node (ref "X4") (pin "5") (pinfunction "KL_5") (pintype "passive"))
    )
    (net (code "63") (name "SDA") (class "Default")
      (node (ref "R59") (pin "1") (pinfunction "1_1") (pintype "passive"))
      (node (ref "SV1") (pin "3") (pinfunction "3_3") (pintype "passive"))
      (node (ref "U1") (pin "36") (pinfunction "PF7_36") (pintype "bidirectional"))
    )
    (net (code "64") (name "SDA_RX") (class "Default")
      (node (ref "U1") (pin "22") (pinfunction "PB11_22") (pintype "bidirectional"))
      (node (ref "X4") (pin "4") (pinfunction "KL_4") (pintype "passive"))
    )
    (net (code "65") (name "SEN1") (class "Default")
      (node (ref "C11") (pin "1") (pinfunction "1_1") (pintype "passive"))
      (node (ref "IC1") (pin "1") (pinfunction "SEN_A_1") (pintype "input"))
      (node (ref "R6") (pin "1") (pinfunction "1_1") (pintype "passive"))
      (node (ref "U1") (pin "10") (pinfunction "PA0_10") (pintype "bidirectional"))
    )
    (net (code "66") (name "SEN2") (class "Default")
      (node (ref "C12") (pin "1") (pinfunction "1_1") (pintype "passive"))
      (node (ref "IC1") (pin "15") (pinfunction "SEN_B_15") (pintype "input"))
      (node (ref "R5") (pin "1") (pinfunction "1_1") (pintype "passive"))
      (node (ref "U1") (pin "11") (pinfunction "PA1_11") (pintype "bidirectional"))
    )
    (net (code "67") (name "SEN3") (class "Default")
      (node (ref "C13") (pin "1") (pinfunction "1_1") (pintype "passive"))
      (node (ref "IC2") (pin "1") (pinfunction "SEN_A_1") (pintype "input"))
      (node (ref "R7") (pin "1") (pinfunction "1_1") (pintype "passive"))
      (node (ref "U1") (pin "12") (pinfunction "PA2_12") (pintype "bidirectional"))
    )
    (net (code "68") (name "SEN4") (class "Default")
      (node (ref "C14") (pin "1") (pinfunction "1_1") (pintype "passive"))
      (node (ref "IC2") (pin "15") (pinfunction "SEN_B_15") (pintype "input"))
      (node (ref "R8") (pin "1") (pinfunction "1_1") (pintype "passive"))
      (node (ref "U1") (pin "13") (pinfunction "PA3_13") (pintype "bidirectional"))
    )
    (net (code "69") (name "SERVO1") (class "Default")
      (node (ref "U3") (pin "7") (pinfunction "A5_7") (pintype "output"))
      (node (ref "X4") (pin "6") (pinfunction "KL_6") (pintype "passive"))
    )
    (net (code "70") (name "SERVO1_UC") (class "Default")
      (node (ref "U1") (pin "29") (pinfunction "PA8_29") (pintype "bidirectional"))
      (node (ref "U3") (pin "17") (pinfunction "B5_17") (pintype "output"))
    )
    (net (code "71") (name "SERVO2") (class "Default")
      (node (ref "U3") (pin "8") (pinfunction "A6_8") (pintype "output"))
      (node (ref "X4") (pin "7") (pinfunction "KL_7") (pintype "passive"))
    )
    (net (code "72") (name "SERVO2_UC") (class "Default")
      (node (ref "U1") (pin "30") (pinfunction "PA9_30") (pintype "bidirectional"))
      (node (ref "U3") (pin "16") (pinfunction "B6_16") (pintype "output"))
    )
    (net (code "73") (name "SERVO3") (class "Default")
      (node (ref "U3") (pin "9") (pinfunction "A7_9") (pintype "output"))
      (node (ref "X4") (pin "8") (pinfunction "KL_8") (pintype "passive"))
    )
    (net (code "74") (name "SERVO3_UC") (class "Default")
      (node (ref "U1") (pin "31") (pinfunction "PA10_31") (pintype "bidirectional"))
      (node (ref "U3") (pin "15") (pinfunction "B7_15") (pintype "output"))
    )
    (net (code "75") (name "SPI1_NSS") (class "Default")
      (node (ref "R61") (pin "1") (pinfunction "1_1") (pintype "passive"))
      (node (ref "SV1") (pin "15") (pinfunction "15_15") (pintype "passive"))
      (node (ref "SV1") (pin "24") (pinfunction "24_24") (pintype "passive"))
      (node (ref "U1") (pin "38") (pinfunction "PA15_38") (pintype "bidirectional"))
    )
    (net (code "76") (name "SWCLK") (class "Default")
      (node (ref "SV1") (pin "22") (pinfunction "22_22") (pintype "passive"))
      (node (ref "U1") (pin "37") (pinfunction "PA14-SWCLK_37") (pintype "bidirectional"))
    )
    (net (code "77") (name "SWDIO") (class "Default")
      (node (ref "SV1") (pin "18") (pinfunction "18_18") (pintype "passive"))
      (node (ref "U1") (pin "34") (pinfunction "PA13-SWDIO_34") (pintype "bidirectional"))
    )
    (net (code "78") (name "VCC") (class "Default")
      (node (ref "C16") (pin "1") (pinfunction "1_1") (pintype "passive"))
      (node (ref "C17") (pin "1") (pinfunction "1_1") (pintype "passive"))
      (node (ref "C5") (pin "+") (pinfunction "+_+") (pintype "passive"))
      (node (ref "C6") (pin "1") (pinfunction "1_1") (pintype "passive"))
      (node (ref "D10") (pin "C") (pinfunction "C_C") (pintype "passive"))
      (node (ref "D11") (pin "C") (pinfunction "C_C") (pintype "passive"))
      (node (ref "D12") (pin "C") (pinfunction "C_C") (pintype "passive"))
      (node (ref "D13") (pin "C") (pinfunction "C_C") (pintype "passive"))
      (node (ref "D2") (pin "C") (pinfunction "C_C") (pintype "passive"))
      (node (ref "D3") (pin "C") (pinfunction "C_C") (pintype "passive"))
      (node (ref "D4") (pin "C") (pinfunction "C_C") (pintype "passive"))
      (node (ref "D5") (pin "C") (pinfunction "C_C") (pintype "passive"))
      (node (ref "IC1") (pin "4") (pinfunction "VS_4") (pintype "power_in"))
      (node (ref "IC2") (pin "4") (pinfunction "VS_4") (pintype "power_in"))
      (node (ref "R45") (pin "2") (pinfunction "2_2") (pintype "passive"))
      (node (ref "U$2") (pin "IN+") (pinfunction "VIN+_IN+") (pintype "input"))
      (node (ref "U$4") (pin "IN+") (pinfunction "VIN+_IN+") (pintype "input"))
      (node (ref "X2") (pin "1") (pinfunction "KL_1") (pintype "passive"))
      (node (ref "X3") (pin "2") (pinfunction "SK_2") (pintype "passive"))
      (node (ref "X7") (pin "2") (pinfunction "K_2") (pintype "passive"))
    )
    (net (code "79") (name "unconnected-(SV1-Pad7)") (class "Default")
      (node (ref "SV1") (pin "7") (pinfunction "7_7") (pintype "passive"))
    )
    (net (code "80") (name "unconnected-(SV1-Pad11)") (class "Default")
      (node (ref "SV1") (pin "11") (pinfunction "11_11") (pintype "passive"))
    )
    (net (code "81") (name "unconnected-(SV1-Pad13)") (class "Default")
      (node (ref "SV1") (pin "13") (pinfunction "13_13") (pintype "passive"))
    )
    (net (code "82") (name "unconnected-(SV1-Pad16)") (class "Default")
      (node (ref "SV1") (pin "16") (pinfunction "16_16") (pintype "passive"))
    )
    (net (code "83") (name "unconnected-(SV1-Pad26)") (class "Default")
      (node (ref "SV1") (pin "26") (pinfunction "26_26") (pintype "passive"))
    )
    (net (code "84") (name "unconnected-(SV1-Pad27)") (class "Default")
      (node (ref "SV1") (pin "27") (pinfunction "27_27") (pintype "passive"))
    )
    (net (code "85") (name "unconnected-(SV1-Pad28)") (class "Default")
      (node (ref "SV1") (pin "28") (pinfunction "28_28") (pintype "passive"))
    )
    (net (code "86") (name "unconnected-(SV1-Pad29)") (class "Default")
      (node (ref "SV1") (pin "29") (pinfunction "29_29") (pintype "passive"))
    )
    (net (code "87") (name "unconnected-(SV1-Pad31)") (class "Default")
      (node (ref "SV1") (pin "31") (pinfunction "31_31") (pintype "passive"))
    )
    (net (code "88") (name "unconnected-(SV1-Pad32)") (class "Default")
      (node (ref "SV1") (pin "32") (pinfunction "32_32") (pintype "passive"))
    )
    (net (code "89") (name "unconnected-(SV1-Pad33)") (class "Default")
      (node (ref "SV1") (pin "33") (pinfunction "33_33") (pintype "passive"))
    )
    (net (code "90") (name "unconnected-(SV1-Pad35)") (class "Default")
      (node (ref "SV1") (pin "35") (pinfunction "35_35") (pintype "passive"))
    )
    (net (code "91") (name "unconnected-(SV1-Pad36)") (class "Default")
      (node (ref "SV1") (pin "36") (pinfunction "36_36") (pintype "passive"))
    )
    (net (code "92") (name "unconnected-(SV1-Pad37)") (class "Default")
      (node (ref "SV1") (pin "37") (pinfunction "37_37") (pintype "passive"))
    )
    (net (code "93") (name "unconnected-(SV1-Pad38)") (class "Default")
      (node (ref "SV1") (pin "38") (pinfunction "38_38") (pintype "passive"))
    )
    (net (code "94") (name "unconnected-(SV1-Pad40)") (class "Default")
      (node (ref "SV1") (pin "40") (pinfunction "40_40") (pintype "passive"))
    )
    (net (code "95") (name "unconnected-(U1A-PF14-OSC32_IN-Pad3)") (class "Default")
      (node (ref "U1") (pin "3") (pinfunction "PF14-OSC32_IN_3") (pintype "bidirectional"))
    )
    (net (code "96") (name "unconnected-(U1A-PF15-OSC32_OUT-Pad4)") (class "Default")
      (node (ref "U1") (pin "4") (pinfunction "PF15-OSC32_OUT_4") (pintype "bidirectional"))
    )
    (net (code "97") (name "unconnected-(U1B-PC13-Pad2)") (class "Default")
      (node (ref "U1") (pin "2") (pinfunction "PC13_2") (pintype "bidirectional"))
    )
    (net (code "98") (name "unconnected-(U1C-PB2-Pad20)") (class "Default")
      (node (ref "U1") (pin "20") (pinfunction "PB2_20") (pintype "bidirectional"))
    )
    (net (code "99") (name "unconnected-(U3-A8-Pad10)") (class "Default")
      (node (ref "U3") (pin "10") (pinfunction "A8_10") (pintype "output"))
    )
    (net (code "100") (name "unconnected-(U3-B8-Pad14)") (class "Default")
      (node (ref "U3") (pin "14") (pinfunction "B8_14") (pintype "output"))
    )
  )
)
